# spi_lcd_booster_dip_v1.net
KiCad netlist of a schematic drawn in EAGLE
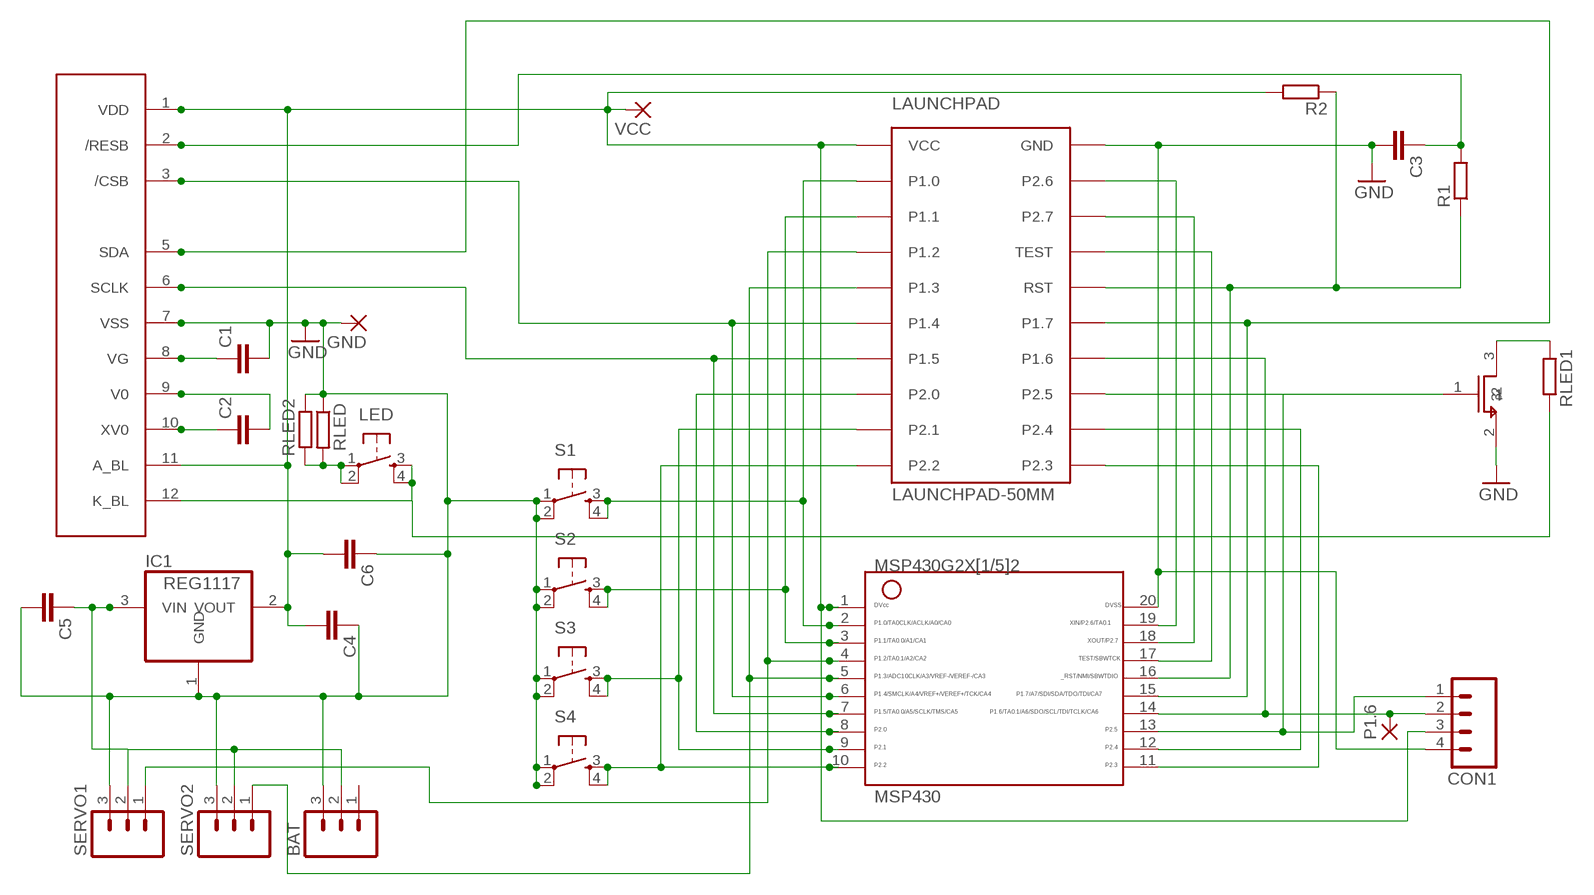
[diagram p0: schematic, sheet 1]

(export (version "E")
  (design (tool "Eeschema 10.0.6"))
  (components
    (comp (ref "BAT")
      (value "M03PTH")
      (footprint "eagle-import:1X03")
      (libsource (lib "eagle-import") (part "M03PTH"))
    )
    (comp (ref "C1")
      (value "CAP1206")
      (footprint "eagle-import:1206")
      (libsource (lib "eagle-import") (part "CAP1206"))
    )
    (comp (ref "C2")
      (value "CAP1206")
      (footprint "eagle-import:1206")
      (libsource (lib "eagle-import") (part "CAP1206"))
    )
    (comp (ref "C3")
      (value "CAP1206")
      (footprint "eagle-import:1206")
      (libsource (lib "eagle-import") (part "CAP1206"))
    )
    (comp (ref "C4")
      (value "CAP1206")
      (footprint "eagle-import:1206")
      (libsource (lib "eagle-import") (part "CAP1206"))
    )
    (comp (ref "C5")
      (value "CAP1206")
      (footprint "eagle-import:1206")
      (libsource (lib "eagle-import") (part "CAP1206"))
    )
    (comp (ref "C6")
      (value "CAP1206")
      (footprint "eagle-import:1206")
      (libsource (lib "eagle-import") (part "CAP1206"))
    )
    (comp (ref "CON1")
      (value "M04PTH")
      (footprint "eagle-import:1X04")
      (libsource (lib "eagle-import") (part "M04PTH"))
    )
    (comp (ref "GND")
      (value "2,15/1,0")
      (footprint "eagle-import:2,15_1,0")
      (libsource (lib "eagle-import") (part "2,15/1,0"))
    )
    (comp (ref "IC1")
      (value "REG1117")
      (footprint "eagle-import:SOT223")
      (libsource (lib "eagle-import") (part "REG1117"))
    )
    (comp (ref "LAUNCHPAD")
      (value "LAUNCHPAD-50MM")
      (footprint "eagle-import:LAUNCHPAD-50MM")
      (libsource (lib "eagle-import") (part "LAUNCHPAD-50MM"))
    )
    (comp (ref "LED")
      (value "TAC_SWITCHPTH")
      (footprint "eagle-import:TACTILE-PTH")
      (libsource (lib "eagle-import") (part "TAC_SWITCHPTH"))
    )
    (comp (ref "LEDSW")
      (value "2N7002PW")
      (footprint "eagle-import:SOT323-R")
      (libsource (lib "eagle-import") (part "2N7002PW"))
    )
    (comp (ref "MSP430")
      (value "G2X[1/5]2---N20")
      (footprint "eagle-import:N20")
      (libsource (lib "eagle-import") (part "G2X[1/5]2---N20"))
    )
    (comp (ref "P1.6")
      (value "2,15/1,0")
      (footprint "eagle-import:2,15_1,0")
      (libsource (lib "eagle-import") (part "2,15/1,0"))
    )
    (comp (ref "R1")
      (value "R-EU_R1206")
      (footprint "eagle-import:R1206")
      (libsource (lib "eagle-import") (part "R-EU_R1206"))
    )
    (comp (ref "R2")
      (value "R-EU_R1206")
      (footprint "eagle-import:R1206")
      (libsource (lib "eagle-import") (part "R-EU_R1206"))
    )
    (comp (ref "RLED")
      (value "R-EU_R1206")
      (footprint "eagle-import:R1206")
      (libsource (lib "eagle-import") (part "R-EU_R1206"))
    )
    (comp (ref "RLED1")
      (value "R-EU_R1206")
      (footprint "eagle-import:R1206")
      (libsource (lib "eagle-import") (part "R-EU_R1206"))
    )
    (comp (ref "RLED2")
      (value "R-EU_0207/10")
      (footprint "eagle-import:0207_10")
      (libsource (lib "eagle-import") (part "R-EU_0207/10"))
    )
    (comp (ref "S1")
      (value "TAC_SWITCHPTH")
      (footprint "eagle-import:TACTILE-PTH")
      (libsource (lib "eagle-import") (part "TAC_SWITCHPTH"))
    )
    (comp (ref "S2")
      (value "TAC_SWITCHPTH")
      (footprint "eagle-import:TACTILE-PTH")
      (libsource (lib "eagle-import") (part "TAC_SWITCHPTH"))
    )
    (comp (ref "S3")
      (value "TAC_SWITCHPTH")
      (footprint "eagle-import:TACTILE-PTH")
      (libsource (lib "eagle-import") (part "TAC_SWITCHPTH"))
    )
    (comp (ref "S4")
      (value "TAC_SWITCHPTH")
      (footprint "eagle-import:TACTILE-PTH")
      (libsource (lib "eagle-import") (part "TAC_SWITCHPTH"))
    )
    (comp (ref "SERVO1")
      (value "M03PTH")
      (footprint "eagle-import:1X03")
      (libsource (lib "eagle-import") (part "M03PTH"))
    )
    (comp (ref "SERVO2")
      (value "M03PTH")
      (footprint "eagle-import:1X03")
      (libsource (lib "eagle-import") (part "M03PTH"))
    )
    (comp (ref "U$1")
      (value "PE9665WRFPE9665WRF-WHOLE")
      (footprint "eagle-import:PE9665WRF")
      (libsource (lib "eagle-import") (part "PE9665WRFPE9665WRF-WHOLE"))
    )
    (comp (ref "VCC")
      (value "2,15/1,0")
      (footprint "eagle-import:2,15_1,0")
      (libsource (lib "eagle-import") (part "2,15/1,0"))
    )
  )
  (nets
    (net (code "1") (name "GND") (class "Default")
      (node (ref "BAT") (pin "3") (pinfunction "3_3") (pintype "passive"))
      (node (ref "C1") (pin "2") (pinfunction "2_2") (pintype "passive"))
      (node (ref "C3") (pin "2") (pinfunction "2_2") (pintype "passive"))
      (node (ref "C4") (pin "1") (pinfunction "1_1") (pintype "passive"))
      (node (ref "C5") (pin "2") (pinfunction "2_2") (pintype "passive"))
      (node (ref "C6") (pin "1") (pinfunction "1_1") (pintype "passive"))
      (node (ref "CON1") (pin "4") (pinfunction "4_4") (pintype "passive"))
      (node (ref "GND") (pin "1") (pinfunction "P_1") (pintype "passive"))
      (node (ref "IC1") (pin "1") (pinfunction "GND_1") (pintype "power_in"))
      (node (ref "LAUNCHPAD") (pin "GND") (pinfunction "GND_GND") (pintype "power_in"))
      (node (ref "LEDSW") (pin "2") (pinfunction "2_2") (pintype "bidirectional"))
      (node (ref "MSP430") (pin "20") (pinfunction "20_20") (pintype "bidirectional"))
      (node (ref "RLED") (pin "1") (pinfunction "1_1") (pintype "passive"))
      (node (ref "RLED2") (pin "2") (pinfunction "2_2") (pintype "passive"))
      (node (ref "S1") (pin "1") (pinfunction "1_1") (pintype "passive"))
      (node (ref "S1") (pin "2") (pinfunction "2_2") (pintype "passive"))
      (node (ref "S2") (pin "1") (pinfunction "1_1") (pintype "passive"))
      (node (ref "S2") (pin "2") (pinfunction "2_2") (pintype "passive"))
      (node (ref "S3") (pin "1") (pinfunction "1_1") (pintype "passive"))
      (node (ref "S3") (pin "2") (pinfunction "2_2") (pintype "passive"))
      (node (ref "S4") (pin "1") (pinfunction "1_1") (pintype "passive"))
      (node (ref "S4") (pin "2") (pinfunction "2_2") (pintype "passive"))
      (node (ref "SERVO1") (pin "3") (pinfunction "3_3") (pintype "passive"))
      (node (ref "SERVO2") (pin "3") (pinfunction "3_3") (pintype "passive"))
      (node (ref "U$1") (pin "7") (pinfunction "VSS_7") (pintype "bidirectional"))
    )
    (net (code "2") (name "Net-(CON1-Pad1)") (class "Default")
      (node (ref "CON1") (pin "1") (pinfunction "1_1") (pintype "passive"))
      (node (ref "LAUNCHPAD") (pin "P2.5") (pinfunction "P2.5_P2.5") (pintype "bidirectional"))
      (node (ref "LEDSW") (pin "1") (pinfunction "1_1") (pintype "bidirectional"))
      (node (ref "MSP430") (pin "13") (pinfunction "13_13") (pintype "bidirectional"))
    )
    (net (code "3") (name "Net-(IC1-VIN)") (class "Default")
      (node (ref "BAT") (pin "2") (pinfunction "2_2") (pintype "passive"))
      (node (ref "C5") (pin "1") (pinfunction "1_1") (pintype "passive"))
      (node (ref "IC1") (pin "3") (pinfunction "VIN_3") (pintype "input"))
      (node (ref "SERVO1") (pin "2") (pinfunction "2_2") (pintype "passive"))
      (node (ref "SERVO2") (pin "2") (pinfunction "2_2") (pintype "passive"))
    )
    (net (code "4") (name "Net-(IC1-VOUT)") (class "Default")
      (node (ref "C4") (pin "2") (pinfunction "2_2") (pintype "passive"))
      (node (ref "C6") (pin "2") (pinfunction "2_2") (pintype "passive"))
      (node (ref "CON1") (pin "3") (pinfunction "3_3") (pintype "passive"))
      (node (ref "IC1") (pin "2") (pinfunction "VOUT_2") (pintype "output"))
      (node (ref "LAUNCHPAD") (pin "VCC") (pinfunction "VCC_VCC") (pintype "power_in"))
      (node (ref "MSP430") (pin "1") (pinfunction "1_1") (pintype "bidirectional"))
      (node (ref "R2") (pin "2") (pinfunction "2_2") (pintype "passive"))
      (node (ref "U$1") (pin "1") (pinfunction "VDD_1") (pintype "bidirectional"))
      (node (ref "U$1") (pin "11") (pinfunction "A_BL_11") (pintype "bidirectional"))
      (node (ref "VCC") (pin "1") (pinfunction "P_1") (pintype "passive"))
    )
    (net (code "5") (name "Net-(LAUNCHPAD-PadP1.0)") (class "Default")
      (node (ref "LAUNCHPAD") (pin "P1.0") (pinfunction "P1.0_P1.0") (pintype "bidirectional"))
      (node (ref "MSP430") (pin "2") (pinfunction "2_2") (pintype "bidirectional"))
      (node (ref "S1") (pin "3") (pinfunction "3_3") (pintype "passive"))
      (node (ref "S1") (pin "4") (pinfunction "4_4") (pintype "passive"))
    )
    (net (code "6") (name "Net-(LAUNCHPAD-PadP1.1)") (class "Default")
      (node (ref "LAUNCHPAD") (pin "P1.1") (pinfunction "P1.1_P1.1") (pintype "bidirectional"))
      (node (ref "MSP430") (pin "3") (pinfunction "3_3") (pintype "bidirectional"))
      (node (ref "S2") (pin "3") (pinfunction "3_3") (pintype "passive"))
      (node (ref "S2") (pin "4") (pinfunction "4_4") (pintype "passive"))
    )
    (net (code "7") (name "Net-(LAUNCHPAD-PadP1.2)") (class "Default")
      (node (ref "LAUNCHPAD") (pin "P1.2") (pinfunction "P1.2_P1.2") (pintype "bidirectional"))
      (node (ref "MSP430") (pin "4") (pinfunction "4_4") (pintype "bidirectional"))
      (node (ref "SERVO1") (pin "1") (pinfunction "1_1") (pintype "passive"))
    )
    (net (code "8") (name "Net-(LAUNCHPAD-PadP1.3)") (class "Default")
      (node (ref "LAUNCHPAD") (pin "P1.3") (pinfunction "P1.3_P1.3") (pintype "bidirectional"))
      (node (ref "MSP430") (pin "5") (pinfunction "5_5") (pintype "bidirectional"))
      (node (ref "SERVO2") (pin "1") (pinfunction "1_1") (pintype "passive"))
    )
    (net (code "9") (name "Net-(LAUNCHPAD-PadP2.0)") (class "Default")
      (node (ref "LAUNCHPAD") (pin "P2.0") (pinfunction "P2.0_P2.0") (pintype "bidirectional"))
      (node (ref "MSP430") (pin "8") (pinfunction "8_8") (pintype "bidirectional"))
    )
    (net (code "10") (name "Net-(LAUNCHPAD-PadP2.1)") (class "Default")
      (node (ref "LAUNCHPAD") (pin "P2.1") (pinfunction "P2.1_P2.1") (pintype "bidirectional"))
      (node (ref "MSP430") (pin "9") (pinfunction "9_9") (pintype "bidirectional"))
      (node (ref "S3") (pin "3") (pinfunction "3_3") (pintype "passive"))
      (node (ref "S3") (pin "4") (pinfunction "4_4") (pintype "passive"))
    )
    (net (code "11") (name "Net-(LAUNCHPAD-PadP2.2)") (class "Default")
      (node (ref "LAUNCHPAD") (pin "P2.2") (pinfunction "P2.2_P2.2") (pintype "bidirectional"))
      (node (ref "MSP430") (pin "10") (pinfunction "10_10") (pintype "bidirectional"))
      (node (ref "S4") (pin "3") (pinfunction "3_3") (pintype "passive"))
      (node (ref "S4") (pin "4") (pinfunction "4_4") (pintype "passive"))
    )
    (net (code "12") (name "Net-(LAUNCHPAD-PadP2.3)") (class "Default")
      (node (ref "LAUNCHPAD") (pin "P2.3") (pinfunction "P2.3_P2.3") (pintype "bidirectional"))
      (node (ref "MSP430") (pin "11") (pinfunction "11_11") (pintype "bidirectional"))
    )
    (net (code "13") (name "Net-(LAUNCHPAD-PadP2.4)") (class "Default")
      (node (ref "LAUNCHPAD") (pin "P2.4") (pinfunction "P2.4_P2.4") (pintype "bidirectional"))
      (node (ref "MSP430") (pin "12") (pinfunction "12_12") (pintype "bidirectional"))
    )
    (net (code "14") (name "Net-(LAUNCHPAD-PadP2.6)") (class "Default")
      (node (ref "LAUNCHPAD") (pin "P2.6") (pinfunction "P2.6_P2.6") (pintype "bidirectional"))
      (node (ref "MSP430") (pin "19") (pinfunction "19_19") (pintype "bidirectional"))
    )
    (net (code "15") (name "Net-(LAUNCHPAD-PadP2.7)") (class "Default")
      (node (ref "LAUNCHPAD") (pin "P2.7") (pinfunction "P2.7_P2.7") (pintype "bidirectional"))
      (node (ref "MSP430") (pin "18") (pinfunction "18_18") (pintype "bidirectional"))
    )
    (net (code "16") (name "Net-(LAUNCHPAD-PadRST)") (class "Default")
      (node (ref "LAUNCHPAD") (pin "RST") (pinfunction "RST_RST") (pintype "bidirectional"))
      (node (ref "MSP430") (pin "16") (pinfunction "16_16") (pintype "bidirectional"))
      (node (ref "R1") (pin "1") (pinfunction "1_1") (pintype "passive"))
      (node (ref "R2") (pin "1") (pinfunction "1_1") (pintype "passive"))
    )
    (net (code "17") (name "Net-(LAUNCHPAD-PadTEST)") (class "Default")
      (node (ref "LAUNCHPAD") (pin "TEST") (pinfunction "TEST_TEST") (pintype "bidirectional"))
      (node (ref "MSP430") (pin "17") (pinfunction "17_17") (pintype "bidirectional"))
    )
    (net (code "18") (name "Net-(LED-Pad1)") (class "Default")
      (node (ref "LED") (pin "1") (pinfunction "1_1") (pintype "passive"))
      (node (ref "LED") (pin "2") (pinfunction "2_2") (pintype "passive"))
      (node (ref "RLED") (pin "2") (pinfunction "2_2") (pintype "passive"))
      (node (ref "RLED2") (pin "1") (pinfunction "1_1") (pintype "passive"))
    )
    (net (code "19") (name "Net-(LEDSW-Pad3)") (class "Default")
      (node (ref "LEDSW") (pin "3") (pinfunction "3_3") (pintype "bidirectional"))
      (node (ref "RLED1") (pin "1") (pinfunction "1_1") (pintype "passive"))
    )
    (net (code "20") (name "Net-(P1.6-P)") (class "Default")
      (node (ref "CON1") (pin "2") (pinfunction "2_2") (pintype "passive"))
      (node (ref "LAUNCHPAD") (pin "P1.6") (pinfunction "P1.6_P1.6") (pintype "bidirectional"))
      (node (ref "MSP430") (pin "14") (pinfunction "14_14") (pintype "bidirectional"))
      (node (ref "P1.6") (pin "1") (pinfunction "P_1") (pintype "passive"))
    )
    (net (code "21") (name "Net-(U$1-K_BL)") (class "Default")
      (node (ref "LED") (pin "3") (pinfunction "3_3") (pintype "passive"))
      (node (ref "LED") (pin "4") (pinfunction "4_4") (pintype "passive"))
      (node (ref "RLED1") (pin "2") (pinfunction "2_2") (pintype "passive"))
      (node (ref "U$1") (pin "12") (pinfunction "K_BL_12") (pintype "bidirectional"))
    )
    (net (code "22") (name "Net-(U$1-SCLK)") (class "Default")
      (node (ref "LAUNCHPAD") (pin "P1.5") (pinfunction "P1.5_P1.5") (pintype "bidirectional"))
      (node (ref "MSP430") (pin "7") (pinfunction "7_7") (pintype "bidirectional"))
      (node (ref "U$1") (pin "6") (pinfunction "SCLK_6") (pintype "bidirectional"))
    )
    (net (code "23") (name "Net-(U$1-SDA)") (class "Default")
      (node (ref "LAUNCHPAD") (pin "P1.7") (pinfunction "P1.7_P1.7") (pintype "bidirectional"))
      (node (ref "MSP430") (pin "15") (pinfunction "15_15") (pintype "bidirectional"))
      (node (ref "U$1") (pin "5") (pinfunction "SDA_5") (pintype "bidirectional"))
    )
    (net (code "24") (name "Net-(U$1-V0)") (class "Default")
      (node (ref "C2") (pin "2") (pinfunction "2_2") (pintype "passive"))
      (node (ref "U$1") (pin "9") (pinfunction "V0_9") (pintype "bidirectional"))
    )
    (net (code "25") (name "Net-(U$1-VG)") (class "Default")
      (node (ref "C1") (pin "1") (pinfunction "1_1") (pintype "passive"))
      (node (ref "U$1") (pin "8") (pinfunction "VG_8") (pintype "bidirectional"))
    )
    (net (code "26") (name "Net-(U$1-XV0)") (class "Default")
      (node (ref "C2") (pin "1") (pinfunction "1_1") (pintype "passive"))
      (node (ref "U$1") (pin "10") (pinfunction "XV0_10") (pintype "bidirectional"))
    )
    (net (code "27") (name "Net-(U$1-{slash}CSB)") (class "Default")
      (node (ref "LAUNCHPAD") (pin "P1.4") (pinfunction "P1.4_P1.4") (pintype "bidirectional"))
      (node (ref "MSP430") (pin "6") (pinfunction "6_6") (pintype "bidirectional"))
      (node (ref "U$1") (pin "3") (pinfunction "/CSB_3") (pintype "bidirectional"))
    )
    (net (code "28") (name "Net-(U$1-{slash}RESB)") (class "Default")
      (node (ref "C3") (pin "1") (pinfunction "1_1") (pintype "passive"))
      (node (ref "R1") (pin "2") (pinfunction "2_2") (pintype "passive"))
      (node (ref "U$1") (pin "2") (pinfunction "/RESB_2") (pintype "bidirectional"))
    )
    (net (code "29") (name "unconnected-(BAT-Pad1)") (class "Default")
      (node (ref "BAT") (pin "1") (pinfunction "1_1") (pintype "passive"))
    )
  )
)
